# Verteilerplatine_Universal_LoetJumper.net
KiCad netlist of a schematic drawn in EAGLE
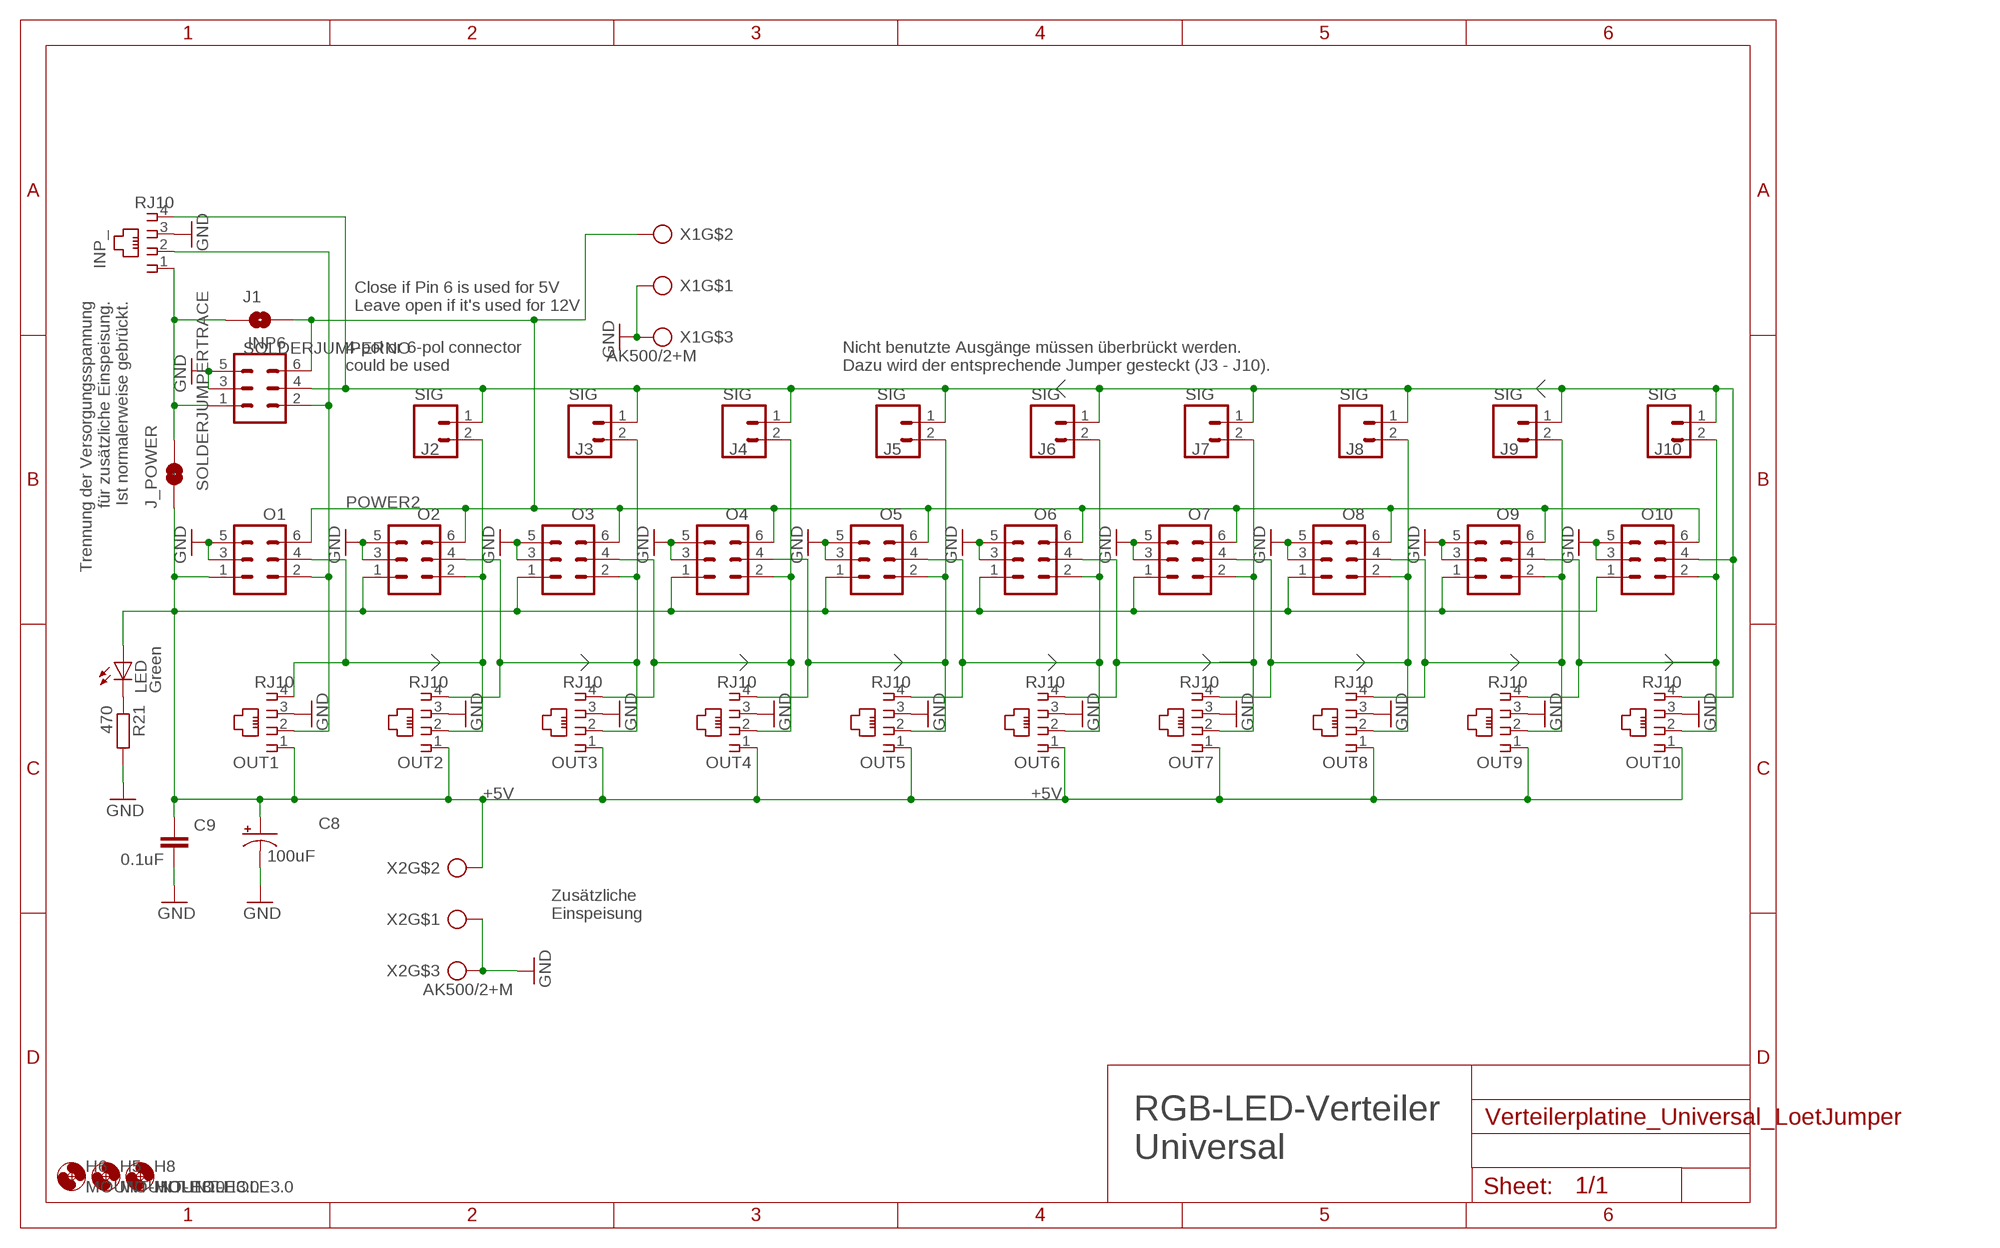
[diagram p0: schematic, sheet 1]

(export (version "E")
  (design (tool "Eeschema 10.0.6"))
  (components
    (comp (ref "C8")
      (value "100uF")
      (footprint "eagle-import:SPARKFUN-CAPACITORS_CPOL-RADIAL-100UF-25V")
      (libsource (lib "eagle-import") (part "SPARKFUN-CAPACITORS_100UF-25V-20%(PTH)"))
    )
    (comp (ref "C9")
      (value "0.1uF")
      (footprint "eagle-import:CAP-PTH-SMALL-KIT")
      (libsource (lib "eagle-import") (part "0.1UF-50V-20%(PTH)KIT-EZ"))
    )
    (comp (ref "H5")
      (value "MOUNT-HOLE3.0")
      (footprint "eagle-import:3,0")
      (libsource (lib "eagle-import") (part "MOUNT-HOLE3.0"))
    )
    (comp (ref "H6")
      (value "MOUNT-HOLE3.0")
      (footprint "eagle-import:3,0")
      (libsource (lib "eagle-import") (part "MOUNT-HOLE3.0"))
    )
    (comp (ref "H8")
      (value "MOUNT-HOLE3.0")
      (footprint "eagle-import:3,0")
      (libsource (lib "eagle-import") (part "MOUNT-HOLE3.0"))
    )
    (comp (ref "INP6")
      (value "ML6")
      (footprint "eagle-import:ML6")
      (libsource (lib "eagle-import") (part "ML6"))
    )
    (comp (ref "INP_")
      (value "RJ10")
      (footprint "eagle-import:RJ10")
      (libsource (lib "eagle-import") (part "RJ10"))
    )
    (comp (ref "J1")
      (value "SOLDERJUMPERNO")
      (footprint "eagle-import:SJ_2S-NO")
      (libsource (lib "eagle-import") (part "SOLDERJUMPERNO"))
    )
    (comp (ref "J2")
      (value "SIG")
      (footprint "eagle-import:1X02")
      (libsource (lib "eagle-import") (part "M02PTH"))
    )
    (comp (ref "J3")
      (value "SIG")
      (footprint "eagle-import:1X02")
      (libsource (lib "eagle-import") (part "M02PTH"))
    )
    (comp (ref "J4")
      (value "SIG")
      (footprint "eagle-import:1X02")
      (libsource (lib "eagle-import") (part "M02PTH"))
    )
    (comp (ref "J5")
      (value "SIG")
      (footprint "eagle-import:1X02")
      (libsource (lib "eagle-import") (part "M02PTH"))
    )
    (comp (ref "J6")
      (value "SIG")
      (footprint "eagle-import:1X02")
      (libsource (lib "eagle-import") (part "M02PTH"))
    )
    (comp (ref "J7")
      (value "SIG")
      (footprint "eagle-import:1X02")
      (libsource (lib "eagle-import") (part "M02PTH"))
    )
    (comp (ref "J8")
      (value "SIG")
      (footprint "eagle-import:1X02")
      (libsource (lib "eagle-import") (part "M02PTH"))
    )
    (comp (ref "J9")
      (value "SIG")
      (footprint "eagle-import:1X02")
      (libsource (lib "eagle-import") (part "M02PTH"))
    )
    (comp (ref "J10")
      (value "SIG")
      (footprint "eagle-import:1X02")
      (libsource (lib "eagle-import") (part "M02PTH"))
    )
    (comp (ref "J_POWER")
      (value "SOLDERJUMPERTRACE")
      (footprint "eagle-import:SJ_2S-TRACE")
      (libsource (lib "eagle-import") (part "SOLDERJUMPERTRACE"))
    )
    (comp (ref "LED")
      (value "Green")
      (footprint "eagle-import:LED_LED3MM")
      (libsource (lib "eagle-import") (part "LED_LED3MM"))
    )
    (comp (ref "O1")
      (value "ML6")
      (footprint "eagle-import:ML6")
      (libsource (lib "eagle-import") (part "ML6"))
    )
    (comp (ref "O2")
      (value "ML6")
      (footprint "eagle-import:ML6")
      (libsource (lib "eagle-import") (part "ML6"))
    )
    (comp (ref "O3")
      (value "ML6")
      (footprint "eagle-import:ML6")
      (libsource (lib "eagle-import") (part "ML6"))
    )
    (comp (ref "O4")
      (value "ML6")
      (footprint "eagle-import:ML6")
      (libsource (lib "eagle-import") (part "ML6"))
    )
    (comp (ref "O5")
      (value "ML6")
      (footprint "eagle-import:ML6")
      (libsource (lib "eagle-import") (part "ML6"))
    )
    (comp (ref "O6")
      (value "ML6")
      (footprint "eagle-import:ML6")
      (libsource (lib "eagle-import") (part "ML6"))
    )
    (comp (ref "O7")
      (value "ML6")
      (footprint "eagle-import:ML6")
      (libsource (lib "eagle-import") (part "ML6"))
    )
    (comp (ref "O8")
      (value "ML6")
      (footprint "eagle-import:ML6")
      (libsource (lib "eagle-import") (part "ML6"))
    )
    (comp (ref "O9")
      (value "ML6")
      (footprint "eagle-import:ML6")
      (libsource (lib "eagle-import") (part "ML6"))
    )
    (comp (ref "O10")
      (value "ML6")
      (footprint "eagle-import:ML6")
      (libsource (lib "eagle-import") (part "ML6"))
    )
    (comp (ref "OUT1")
      (value "RJ10")
      (footprint "eagle-import:RJ10")
      (libsource (lib "eagle-import") (part "RJ10"))
    )
    (comp (ref "OUT2")
      (value "RJ10")
      (footprint "eagle-import:RJ10")
      (libsource (lib "eagle-import") (part "RJ10"))
    )
    (comp (ref "OUT3")
      (value "RJ10")
      (footprint "eagle-import:RJ10")
      (libsource (lib "eagle-import") (part "RJ10"))
    )
    (comp (ref "OUT4")
      (value "RJ10")
      (footprint "eagle-import:RJ10")
      (libsource (lib "eagle-import") (part "RJ10"))
    )
    (comp (ref "OUT5")
      (value "RJ10")
      (footprint "eagle-import:RJ10")
      (libsource (lib "eagle-import") (part "RJ10"))
    )
    (comp (ref "OUT6")
      (value "RJ10")
      (footprint "eagle-import:RJ10")
      (libsource (lib "eagle-import") (part "RJ10"))
    )
    (comp (ref "OUT7")
      (value "RJ10")
      (footprint "eagle-import:RJ10")
      (libsource (lib "eagle-import") (part "RJ10"))
    )
    (comp (ref "OUT8")
      (value "RJ10")
      (footprint "eagle-import:RJ10")
      (libsource (lib "eagle-import") (part "RJ10"))
    )
    (comp (ref "OUT9")
      (value "RJ10")
      (footprint "eagle-import:RJ10")
      (libsource (lib "eagle-import") (part "RJ10"))
    )
    (comp (ref "OUT10")
      (value "RJ10")
      (footprint "eagle-import:RJ10")
      (libsource (lib "eagle-import") (part "RJ10"))
    )
    (comp (ref "R21")
      (value "470")
      (footprint "eagle-import:RCL_0207_2V")
      (libsource (lib "eagle-import") (part "RCL_R-EU_0207/2V"))
    )
    (comp (ref "X1")
      (value "AK500/2+M")
      (footprint "eagle-import:AK500_2+M")
      (libsource (lib "eagle-import") (part "AK500/2+M"))
    )
    (comp (ref "X2")
      (value "AK500/2+M")
      (footprint "eagle-import:AK500_2+M")
      (libsource (lib "eagle-import") (part "AK500/2+M"))
    )
  )
  (nets
    (net (code "1") (name "/POWER2") (class "Default")
      (node (ref "INP6") (pin "6") (pinfunction "6_6") (pintype "passive"))
      (node (ref "J1") (pin "2") (pinfunction "2_2") (pintype "passive"))
      (node (ref "O1") (pin "6") (pinfunction "6_6") (pintype "passive"))
      (node (ref "O10") (pin "6") (pinfunction "6_6") (pintype "passive"))
      (node (ref "O2") (pin "6") (pinfunction "6_6") (pintype "passive"))
      (node (ref "O3") (pin "6") (pinfunction "6_6") (pintype "passive"))
      (node (ref "O4") (pin "6") (pinfunction "6_6") (pintype "passive"))
      (node (ref "O5") (pin "6") (pinfunction "6_6") (pintype "passive"))
      (node (ref "O6") (pin "6") (pinfunction "6_6") (pintype "passive"))
      (node (ref "O7") (pin "6") (pinfunction "6_6") (pintype "passive"))
      (node (ref "O8") (pin "6") (pinfunction "6_6") (pintype "passive"))
      (node (ref "O9") (pin "6") (pinfunction "6_6") (pintype "passive"))
      (node (ref "X1") (pin "2") (pinfunction "KL_2") (pintype "passive"))
    )
    (net (code "2") (name "GND") (class "Default")
      (node (ref "C8") (pin "2") (pinfunction "-_2") (pintype "passive"))
      (node (ref "C9") (pin "1") (pinfunction "1_1") (pintype "passive"))
      (node (ref "INP6") (pin "3") (pinfunction "3_3") (pintype "passive"))
      (node (ref "INP6") (pin "5") (pinfunction "5_5") (pintype "passive"))
      (node (ref "INP_") (pin "3") (pinfunction "3_3") (pintype "passive"))
      (node (ref "O1") (pin "3") (pinfunction "3_3") (pintype "passive"))
      (node (ref "O1") (pin "5") (pinfunction "5_5") (pintype "passive"))
      (node (ref "O10") (pin "3") (pinfunction "3_3") (pintype "passive"))
      (node (ref "O10") (pin "5") (pinfunction "5_5") (pintype "passive"))
      (node (ref "O2") (pin "3") (pinfunction "3_3") (pintype "passive"))
      (node (ref "O2") (pin "5") (pinfunction "5_5") (pintype "passive"))
      (node (ref "O3") (pin "3") (pinfunction "3_3") (pintype "passive"))
      (node (ref "O3") (pin "5") (pinfunction "5_5") (pintype "passive"))
      (node (ref "O4") (pin "3") (pinfunction "3_3") (pintype "passive"))
      (node (ref "O4") (pin "5") (pinfunction "5_5") (pintype "passive"))
      (node (ref "O5") (pin "3") (pinfunction "3_3") (pintype "passive"))
      (node (ref "O5") (pin "5") (pinfunction "5_5") (pintype "passive"))
      (node (ref "O6") (pin "3") (pinfunction "3_3") (pintype "passive"))
      (node (ref "O6") (pin "5") (pinfunction "5_5") (pintype "passive"))
      (node (ref "O7") (pin "3") (pinfunction "3_3") (pintype "passive"))
      (node (ref "O7") (pin "5") (pinfunction "5_5") (pintype "passive"))
      (node (ref "O8") (pin "3") (pinfunction "3_3") (pintype "passive"))
      (node (ref "O8") (pin "5") (pinfunction "5_5") (pintype "passive"))
      (node (ref "O9") (pin "3") (pinfunction "3_3") (pintype "passive"))
      (node (ref "O9") (pin "5") (pinfunction "5_5") (pintype "passive"))
      (node (ref "OUT1") (pin "3") (pinfunction "3_3") (pintype "passive"))
      (node (ref "OUT10") (pin "3") (pinfunction "3_3") (pintype "passive"))
      (node (ref "OUT2") (pin "3") (pinfunction "3_3") (pintype "passive"))
      (node (ref "OUT3") (pin "3") (pinfunction "3_3") (pintype "passive"))
      (node (ref "OUT4") (pin "3") (pinfunction "3_3") (pintype "passive"))
      (node (ref "OUT5") (pin "3") (pinfunction "3_3") (pintype "passive"))
      (node (ref "OUT6") (pin "3") (pinfunction "3_3") (pintype "passive"))
      (node (ref "OUT7") (pin "3") (pinfunction "3_3") (pintype "passive"))
      (node (ref "OUT8") (pin "3") (pinfunction "3_3") (pintype "passive"))
      (node (ref "OUT9") (pin "3") (pinfunction "3_3") (pintype "passive"))
      (node (ref "R21") (pin "2") (pinfunction "2_2") (pintype "passive"))
      (node (ref "X1") (pin "1") (pinfunction "KL_1") (pintype "passive"))
      (node (ref "X1") (pin "M") (pinfunction "KL_M") (pintype "passive"))
      (node (ref "X2") (pin "1") (pinfunction "KL_1") (pintype "passive"))
      (node (ref "X2") (pin "M") (pinfunction "KL_M") (pintype "passive"))
    )
    (net (code "3") (name "Net-(C8-+)") (class "Default")
      (node (ref "C8") (pin "1") (pinfunction "+_1") (pintype "passive"))
      (node (ref "C9") (pin "2") (pinfunction "2_2") (pintype "passive"))
      (node (ref "J_POWER") (pin "1") (pinfunction "1_1") (pintype "passive"))
      (node (ref "LED") (pin "A") (pinfunction "A_A") (pintype "passive"))
      (node (ref "O1") (pin "1") (pinfunction "1_1") (pintype "passive"))
      (node (ref "O10") (pin "1") (pinfunction "1_1") (pintype "passive"))
      (node (ref "O2") (pin "1") (pinfunction "1_1") (pintype "passive"))
      (node (ref "O3") (pin "1") (pinfunction "1_1") (pintype "passive"))
      (node (ref "O4") (pin "1") (pinfunction "1_1") (pintype "passive"))
      (node (ref "O5") (pin "1") (pinfunction "1_1") (pintype "passive"))
      (node (ref "O6") (pin "1") (pinfunction "1_1") (pintype "passive"))
      (node (ref "O7") (pin "1") (pinfunction "1_1") (pintype "passive"))
      (node (ref "O8") (pin "1") (pinfunction "1_1") (pintype "passive"))
      (node (ref "O9") (pin "1") (pinfunction "1_1") (pintype "passive"))
      (node (ref "OUT1") (pin "1") (pinfunction "1_1") (pintype "passive"))
      (node (ref "OUT10") (pin "1") (pinfunction "1_1") (pintype "passive"))
      (node (ref "OUT2") (pin "1") (pinfunction "1_1") (pintype "passive"))
      (node (ref "OUT3") (pin "1") (pinfunction "1_1") (pintype "passive"))
      (node (ref "OUT4") (pin "1") (pinfunction "1_1") (pintype "passive"))
      (node (ref "OUT5") (pin "1") (pinfunction "1_1") (pintype "passive"))
      (node (ref "OUT6") (pin "1") (pinfunction "1_1") (pintype "passive"))
      (node (ref "OUT7") (pin "1") (pinfunction "1_1") (pintype "passive"))
      (node (ref "OUT8") (pin "1") (pinfunction "1_1") (pintype "passive"))
      (node (ref "OUT9") (pin "1") (pinfunction "1_1") (pintype "passive"))
      (node (ref "X2") (pin "2") (pinfunction "KL_2") (pintype "passive"))
    )
    (net (code "4") (name "Net-(INP6-Pad1)") (class "Default")
      (node (ref "INP6") (pin "1") (pinfunction "1_1") (pintype "passive"))
      (node (ref "INP_") (pin "1") (pinfunction "1_1") (pintype "passive"))
      (node (ref "J1") (pin "1") (pinfunction "1_1") (pintype "passive"))
      (node (ref "J_POWER") (pin "2") (pinfunction "2_2") (pintype "passive"))
    )
    (net (code "5") (name "Net-(INP6-Pad2)") (class "Default")
      (node (ref "INP6") (pin "2") (pinfunction "2_2") (pintype "passive"))
      (node (ref "INP_") (pin "2") (pinfunction "2_2") (pintype "passive"))
      (node (ref "O1") (pin "2") (pinfunction "2_2") (pintype "passive"))
      (node (ref "OUT1") (pin "2") (pinfunction "2_2") (pintype "passive"))
    )
    (net (code "6") (name "Net-(INP6-Pad4)") (class "Default")
      (node (ref "INP6") (pin "4") (pinfunction "4_4") (pintype "passive"))
      (node (ref "INP_") (pin "4") (pinfunction "4_4") (pintype "passive"))
      (node (ref "J10") (pin "1") (pinfunction "1_1") (pintype "passive"))
      (node (ref "J2") (pin "1") (pinfunction "1_1") (pintype "passive"))
      (node (ref "J3") (pin "1") (pinfunction "1_1") (pintype "passive"))
      (node (ref "J4") (pin "1") (pinfunction "1_1") (pintype "passive"))
      (node (ref "J5") (pin "1") (pinfunction "1_1") (pintype "passive"))
      (node (ref "J6") (pin "1") (pinfunction "1_1") (pintype "passive"))
      (node (ref "J7") (pin "1") (pinfunction "1_1") (pintype "passive"))
      (node (ref "J8") (pin "1") (pinfunction "1_1") (pintype "passive"))
      (node (ref "J9") (pin "1") (pinfunction "1_1") (pintype "passive"))
      (node (ref "O10") (pin "4") (pinfunction "4_4") (pintype "passive"))
      (node (ref "OUT10") (pin "4") (pinfunction "4_4") (pintype "passive"))
    )
    (net (code "7") (name "Net-(J2-Pad2)") (class "Default")
      (node (ref "J2") (pin "2") (pinfunction "2_2") (pintype "passive"))
      (node (ref "O1") (pin "4") (pinfunction "4_4") (pintype "passive"))
      (node (ref "O2") (pin "2") (pinfunction "2_2") (pintype "passive"))
      (node (ref "OUT1") (pin "4") (pinfunction "4_4") (pintype "passive"))
      (node (ref "OUT2") (pin "2") (pinfunction "2_2") (pintype "passive"))
    )
    (net (code "8") (name "Net-(J3-Pad2)") (class "Default")
      (node (ref "J3") (pin "2") (pinfunction "2_2") (pintype "passive"))
      (node (ref "O2") (pin "4") (pinfunction "4_4") (pintype "passive"))
      (node (ref "O3") (pin "2") (pinfunction "2_2") (pintype "passive"))
      (node (ref "OUT2") (pin "4") (pinfunction "4_4") (pintype "passive"))
      (node (ref "OUT3") (pin "2") (pinfunction "2_2") (pintype "passive"))
    )
    (net (code "9") (name "Net-(J4-Pad2)") (class "Default")
      (node (ref "J4") (pin "2") (pinfunction "2_2") (pintype "passive"))
      (node (ref "O3") (pin "4") (pinfunction "4_4") (pintype "passive"))
      (node (ref "O4") (pin "2") (pinfunction "2_2") (pintype "passive"))
      (node (ref "OUT3") (pin "4") (pinfunction "4_4") (pintype "passive"))
      (node (ref "OUT4") (pin "2") (pinfunction "2_2") (pintype "passive"))
    )
    (net (code "10") (name "Net-(J5-Pad2)") (class "Default")
      (node (ref "J5") (pin "2") (pinfunction "2_2") (pintype "passive"))
      (node (ref "O4") (pin "4") (pinfunction "4_4") (pintype "passive"))
      (node (ref "O5") (pin "2") (pinfunction "2_2") (pintype "passive"))
      (node (ref "OUT4") (pin "4") (pinfunction "4_4") (pintype "passive"))
      (node (ref "OUT5") (pin "2") (pinfunction "2_2") (pintype "passive"))
    )
    (net (code "11") (name "Net-(J6-Pad2)") (class "Default")
      (node (ref "J6") (pin "2") (pinfunction "2_2") (pintype "passive"))
      (node (ref "O5") (pin "4") (pinfunction "4_4") (pintype "passive"))
      (node (ref "O6") (pin "2") (pinfunction "2_2") (pintype "passive"))
      (node (ref "OUT5") (pin "4") (pinfunction "4_4") (pintype "passive"))
      (node (ref "OUT6") (pin "2") (pinfunction "2_2") (pintype "passive"))
    )
    (net (code "12") (name "Net-(J7-Pad2)") (class "Default")
      (node (ref "J7") (pin "2") (pinfunction "2_2") (pintype "passive"))
      (node (ref "O6") (pin "4") (pinfunction "4_4") (pintype "passive"))
      (node (ref "O7") (pin "2") (pinfunction "2_2") (pintype "passive"))
      (node (ref "OUT6") (pin "4") (pinfunction "4_4") (pintype "passive"))
      (node (ref "OUT7") (pin "2") (pinfunction "2_2") (pintype "passive"))
    )
    (net (code "13") (name "Net-(J8-Pad2)") (class "Default")
      (node (ref "J8") (pin "2") (pinfunction "2_2") (pintype "passive"))
      (node (ref "O7") (pin "4") (pinfunction "4_4") (pintype "passive"))
      (node (ref "O8") (pin "2") (pinfunction "2_2") (pintype "passive"))
      (node (ref "OUT7") (pin "4") (pinfunction "4_4") (pintype "passive"))
      (node (ref "OUT8") (pin "2") (pinfunction "2_2") (pintype "passive"))
    )
    (net (code "14") (name "Net-(J9-Pad2)") (class "Default")
      (node (ref "J9") (pin "2") (pinfunction "2_2") (pintype "passive"))
      (node (ref "O8") (pin "4") (pinfunction "4_4") (pintype "passive"))
      (node (ref "O9") (pin "2") (pinfunction "2_2") (pintype "passive"))
      (node (ref "OUT8") (pin "4") (pinfunction "4_4") (pintype "passive"))
      (node (ref "OUT9") (pin "2") (pinfunction "2_2") (pintype "passive"))
    )
    (net (code "15") (name "Net-(J10-Pad2)") (class "Default")
      (node (ref "J10") (pin "2") (pinfunction "2_2") (pintype "passive"))
      (node (ref "O10") (pin "2") (pinfunction "2_2") (pintype "passive"))
      (node (ref "O9") (pin "4") (pinfunction "4_4") (pintype "passive"))
      (node (ref "OUT10") (pin "2") (pinfunction "2_2") (pintype "passive"))
      (node (ref "OUT9") (pin "4") (pinfunction "4_4") (pintype "passive"))
    )
    (net (code "16") (name "Net-(LED-C)") (class "Default")
      (node (ref "LED") (pin "K") (pinfunction "C_K") (pintype "passive"))
      (node (ref "R21") (pin "1") (pinfunction "1_1") (pintype "passive"))
    )
  )
)
